# atmg32.net
KiCad netlist of a schematic drawn in Altium Designer
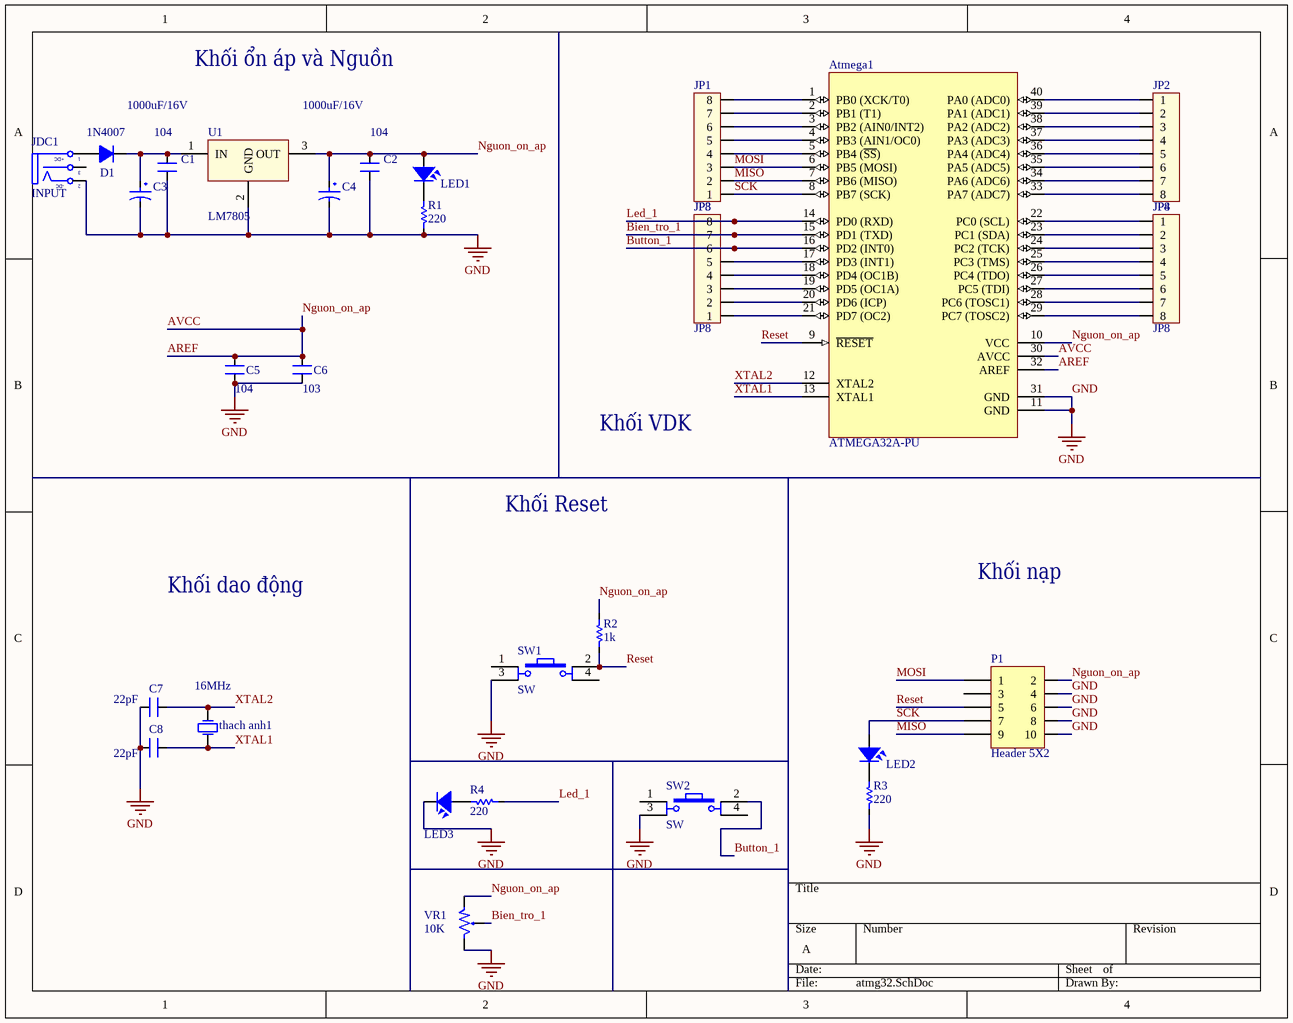
[diagram p0: atmg32.SchDoc]

(export (version "E")
  (design (tool "Eeschema 10.0.6"))
  (components
    (comp (ref "Atmega1")
      (value "ATMEGA32A-PU")
      (footprint "DIP 40")
      (description "8-Bit AVR Microcontroller with 32K Bytes of In-System Programmable Flash Memory")
      (fields (field (name "PUBLISHER") "Altium Limited"))
      (libsource (lib "Library_NguyenThanhPhong") (part "ATMEGA32A-PU"))
    )
    (comp (ref "C1")
      (value "104")
      (footprint "CN0")
      (description "Ceramic capacitor")
      (libsource (lib "Library_NguyenThanhPhong") (part "CN0"))
    )
    (comp (ref "C2")
      (value "104")
      (footprint "CN0")
      (description "Ceramic capacitor")
      (libsource (lib "Library_NguyenThanhPhong") (part "CN0"))
    )
    (comp (ref "C3")
      (value "1000uF/16V")
      (footprint "CAP 10x16x5 CURVE")
      (libsource (lib "Library_NguyenThanhPhong") (part "CAP 10x16mm"))
    )
    (comp (ref "C4")
      (value "1000uF/16V")
      (footprint "CAP 10x16x5 CURVE")
      (libsource (lib "Library_NguyenThanhPhong") (part "CAP 10x16mm"))
    )
    (comp (ref "C5")
      (value "104")
      (footprint "CN0")
      (description "Ceramic capacitor")
      (libsource (lib "Library_NguyenThanhPhong") (part "CN0"))
    )
    (comp (ref "C6")
      (value "103")
      (footprint "CN0")
      (description "Ceramic capacitor")
      (libsource (lib "Library_NguyenThanhPhong") (part "CN0"))
    )
    (comp (ref "C7")
      (value "22pF")
      (footprint "CN0")
      (description "Ceramic capacitor")
      (libsource (lib "Library_NguyenThanhPhong") (part "CN0"))
    )
    (comp (ref "C8")
      (value "22pF")
      (footprint "CN0")
      (description "Ceramic capacitor")
      (libsource (lib "Library_NguyenThanhPhong") (part "CN0"))
    )
    (comp (ref "D1")
      (value "1N4007")
      (footprint "1N4007")
      (description "Diode 1N4007 1A 1000V")
      (libsource (lib "Library_NguyenThanhPhong") (part "1N4007"))
    )
    (comp (ref "JDC1")
      (value "INPUT")
      (footprint "DC-IN")
      (description "Jac DC input")
      (libsource (lib "Library_NguyenThanhPhong") (part "DCIN"))
    )
    (comp (ref "JP1")
      (value "JP8")
      (footprint "XH2.54-8P")
      (description "Header duc 8, Connector 8, Header 8")
      (libsource (lib "Library_NguyenThanhPhong") (part "Con8"))
    )
    (comp (ref "JP2")
      (value "JP8")
      (footprint "XH2.54-8P")
      (description "Header duc 8, Connector 8, Header 8")
      (libsource (lib "") (part "Con8_1"))
    )
    (comp (ref "JP3")
      (value "JP8")
      (footprint "XH2.54-8P")
      (description "Header duc 8, Connector 8, Header 8")
      (libsource (lib "Library_NguyenThanhPhong") (part "Con8"))
    )
    (comp (ref "JP4")
      (value "JP8")
      (footprint "XH2.54-8P")
      (description "Header duc 8, Connector 8, Header 8")
      (libsource (lib "") (part "Con8_1"))
    )
    (comp (ref "LED1")
      (value "LED")
      (footprint "LED-5MM-WHITE")
      (description "LED Single")
      (libsource (lib "Library_NguyenThanhPhong") (part "LED"))
    )
    (comp (ref "LED2")
      (value "LED")
      (footprint "LED-5MM-WHITE")
      (description "LED Single")
      (libsource (lib "Library_NguyenThanhPhong") (part "LED"))
    )
    (comp (ref "LED3")
      (value "LED")
      (footprint "LED-5MM-WHITE")
      (description "LED Single")
      (libsource (lib "Library_NguyenThanhPhong") (part "LED"))
    )
    (comp (ref "P1")
      (value "Header 5X2")
      (footprint "HDR2X5")
      (description "Header, 5-Pin, Dual row")
      (fields (field (name "PUBLISHER") "Altium Limited"))
      (libsource (lib "Miscellaneous Connectors") (part "Header 5X2"))
    )
    (comp (ref "R1")
      (value "220")
      (footprint "RES-1/4W")
      (description "Tro cam")
      (libsource (lib "Library_NguyenThanhPhong") (part "Res1/4W"))
    )
    (comp (ref "R2")
      (value "1k")
      (footprint "RES-1/4W")
      (description "Tro cam")
      (libsource (lib "Library_NguyenThanhPhong") (part "Res1/4W"))
    )
    (comp (ref "R3")
      (value "220")
      (footprint "RES-1/4W")
      (description "Tro cam")
      (libsource (lib "Library_NguyenThanhPhong") (part "Res1/4W"))
    )
    (comp (ref "R4")
      (value "220")
      (footprint "RES-1/4W")
      (description "Tro cam")
      (libsource (lib "Library_NguyenThanhPhong") (part "Res1/4W"))
    )
    (comp (ref "SW1")
      (value "SW")
      (footprint "BUTTON 12x12x5 4P DIP")
      (description "Switch button 4 pin 12x12mm")
      (libsource (lib "Library_NguyenThanhPhong") (part "SW4 12x12"))
    )
    (comp (ref "SW2")
      (value "SW")
      (footprint "BUTTON 12x12x5 4P DIP")
      (description "Switch button 4 pin 12x12mm")
      (libsource (lib "Library_NguyenThanhPhong") (part "SW4 12x12"))
    )
    (comp (ref "thach anh1")
      (value "16MHz")
      (footprint "CRYSTAL DIP")
      (description "Thach anh")
      (fields (field (name "PUBLISHER") "Altium Limited"))
      (libsource (lib "Library_NguyenThanhPhong") (part "Crystal"))
    )
    (comp (ref "U1")
      (value "LM7805")
      (footprint "TO 220+Heatsink 21x15x10mm")
      (description "On ap +, from + 5 to + 24VDC")
      (libsource (lib "Library_NguyenThanhPhong") (part "LM78xx"))
    )
    (comp (ref "VR1")
      (value "10K")
      (footprint "VR-RM065")
      (description "Var Resistor")
      (libsource (lib "Library_NguyenThanhPhong") (part "VR"))
    )
  )
  (nets
    (net (code "1") (name "/AREF") (class "Default")
      (node (ref "Atmega1") (pin "10") (pinfunction "VCC_10") (pintype "power_in"))
      (node (ref "Atmega1") (pin "30") (pinfunction "AVCC_30") (pintype "power_in"))
      (node (ref "Atmega1") (pin "32") (pinfunction "AREF_32") (pintype "passive"))
      (node (ref "C2") (pin "2") (pinfunction "2_2") (pintype "passive"))
      (node (ref "C4") (pin "1") (pinfunction "1_1") (pintype "passive"))
      (node (ref "C5") (pin "2") (pinfunction "2_2") (pintype "passive"))
      (node (ref "C6") (pin "2") (pinfunction "2_2") (pintype "passive"))
      (node (ref "LED1") (pin "1") (pinfunction "1_1") (pintype "passive"))
      (node (ref "P1") (pin "2") (pinfunction "2_2") (pintype "passive"))
      (node (ref "R2") (pin "2") (pinfunction "2_2") (pintype "passive"))
      (node (ref "U1") (pin "3") (pinfunction "OUT_3") (pintype "passive"))
      (node (ref "VR1") (pin "1") (pinfunction "1_1") (pintype "passive"))
    )
    (net (code "2") (name "/Bien_tro_1") (class "Default")
      (node (ref "Atmega1") (pin "15") (pinfunction "PD1_(TXD)_15") (pintype "bidirectional"))
      (node (ref "JP3") (pin "7") (pinfunction "7_7") (pintype "passive"))
      (node (ref "VR1") (pin "2") (pinfunction "2_2") (pintype "passive"))
    )
    (net (code "3") (name "/Button_1") (class "Default")
      (node (ref "Atmega1") (pin "16") (pinfunction "PD2_(INT0)_16") (pintype "bidirectional"))
      (node (ref "JP3") (pin "6") (pinfunction "6_6") (pintype "passive"))
      (node (ref "SW2") (pin "2") (pintype "passive"))
    )
    (net (code "4") (name "/Led_1") (class "Default")
      (node (ref "Atmega1") (pin "14") (pinfunction "PD0_(RXD)_14") (pintype "bidirectional"))
      (node (ref "JP3") (pin "8") (pinfunction "8_8") (pintype "passive"))
      (node (ref "R4") (pin "1") (pinfunction "1_1") (pintype "passive"))
    )
    (net (code "5") (name "/MISO") (class "Default")
      (node (ref "Atmega1") (pin "7") (pinfunction "PB6_(MISO)_7") (pintype "bidirectional"))
      (node (ref "JP1") (pin "2") (pinfunction "2_2") (pintype "passive"))
      (node (ref "P1") (pin "9") (pinfunction "9_9") (pintype "passive"))
    )
    (net (code "6") (name "/MOSI") (class "Default")
      (node (ref "Atmega1") (pin "6") (pinfunction "PB5_(MOSI)_6") (pintype "bidirectional"))
      (node (ref "JP1") (pin "3") (pinfunction "3_3") (pintype "passive"))
      (node (ref "P1") (pin "1") (pinfunction "1_1") (pintype "passive"))
    )
    (net (code "7") (name "/Reset") (class "Default")
      (node (ref "Atmega1") (pin "9") (pinfunction "~{RESET}_9") (pintype "input"))
      (node (ref "P1") (pin "5") (pinfunction "5_5") (pintype "passive"))
      (node (ref "R2") (pin "1") (pinfunction "1_1") (pintype "passive"))
      (node (ref "SW1") (pin "2") (pintype "passive"))
    )
    (net (code "8") (name "/SCK") (class "Default")
      (node (ref "Atmega1") (pin "8") (pinfunction "PB7_(SCK)_8") (pintype "bidirectional"))
      (node (ref "JP1") (pin "1") (pinfunction "1_1") (pintype "passive"))
      (node (ref "LED2") (pin "1") (pinfunction "1_1") (pintype "passive"))
      (node (ref "P1") (pin "7") (pinfunction "7_7") (pintype "passive"))
    )
    (net (code "9") (name "/XTAL1") (class "Default")
      (node (ref "Atmega1") (pin "13") (pinfunction "XTAL1_13") (pintype "passive"))
      (node (ref "C8") (pin "1") (pinfunction "1_1") (pintype "passive"))
      (node (ref "thach anh1") (pin "1") (pinfunction "OSC1_1") (pintype "passive"))
    )
    (net (code "10") (name "/XTAL2") (class "Default")
      (node (ref "Atmega1") (pin "12") (pinfunction "XTAL2_12") (pintype "passive"))
      (node (ref "C7") (pin "1") (pinfunction "1_1") (pintype "passive"))
      (node (ref "thach anh1") (pin "2") (pinfunction "OSC2_2") (pintype "passive"))
    )
    (net (code "11") (name "GND") (class "Default")
      (node (ref "Atmega1") (pin "11") (pinfunction "GND_11") (pintype "power_in"))
      (node (ref "Atmega1") (pin "31") (pinfunction "GND_31") (pintype "power_in"))
      (node (ref "C1") (pin "1") (pinfunction "1_1") (pintype "passive"))
      (node (ref "C2") (pin "1") (pinfunction "1_1") (pintype "passive"))
      (node (ref "C3") (pin "2") (pinfunction "2_2") (pintype "passive"))
      (node (ref "C4") (pin "2") (pinfunction "2_2") (pintype "passive"))
      (node (ref "C5") (pin "1") (pinfunction "1_1") (pintype "passive"))
      (node (ref "C6") (pin "1") (pinfunction "1_1") (pintype "passive"))
      (node (ref "C7") (pin "2") (pinfunction "2_2") (pintype "passive"))
      (node (ref "C8") (pin "2") (pinfunction "2_2") (pintype "passive"))
      (node (ref "JDC1") (pin "2") (pinfunction "TN_2") (pintype "passive"))
      (node (ref "LED3") (pin "2") (pinfunction "2_2") (pintype "passive"))
      (node (ref "P1") (pin "10") (pinfunction "10_10") (pintype "passive"))
      (node (ref "P1") (pin "4") (pinfunction "4_4") (pintype "passive"))
      (node (ref "P1") (pin "6") (pinfunction "6_6") (pintype "passive"))
      (node (ref "P1") (pin "8") (pinfunction "8_8") (pintype "passive"))
      (node (ref "R1") (pin "1") (pinfunction "1_1") (pintype "passive"))
      (node (ref "R3") (pin "1") (pinfunction "1_1") (pintype "passive"))
      (node (ref "SW1") (pin "3") (pintype "passive"))
      (node (ref "SW2") (pin "3") (pintype "passive"))
      (node (ref "U1") (pin "2") (pinfunction "GND_2") (pintype "passive"))
      (node (ref "VR1") (pin "3") (pinfunction "3_3") (pintype "passive"))
    )
    (net (code "12") (name "Net-(Atmega1-PA0_(ADC0))") (class "Default")
      (node (ref "Atmega1") (pin "40") (pinfunction "PA0_(ADC0)_40") (pintype "bidirectional"))
      (node (ref "JP2") (pin "1") (pinfunction "1_1") (pintype "passive"))
    )
    (net (code "13") (name "Net-(Atmega1-PA1_(ADC1))") (class "Default")
      (node (ref "Atmega1") (pin "39") (pinfunction "PA1_(ADC1)_39") (pintype "bidirectional"))
      (node (ref "JP2") (pin "2") (pinfunction "2_2") (pintype "passive"))
    )
    (net (code "14") (name "Net-(Atmega1-PA2_(ADC2))") (class "Default")
      (node (ref "Atmega1") (pin "38") (pinfunction "PA2_(ADC2)_38") (pintype "bidirectional"))
      (node (ref "JP2") (pin "3") (pinfunction "3_3") (pintype "passive"))
    )
    (net (code "15") (name "Net-(Atmega1-PA3_(ADC3))") (class "Default")
      (node (ref "Atmega1") (pin "37") (pinfunction "PA3_(ADC3)_37") (pintype "bidirectional"))
      (node (ref "JP2") (pin "4") (pinfunction "4_4") (pintype "passive"))
    )
    (net (code "16") (name "Net-(Atmega1-PA4_(ADC4))") (class "Default")
      (node (ref "Atmega1") (pin "36") (pinfunction "PA4_(ADC4)_36") (pintype "bidirectional"))
      (node (ref "JP2") (pin "5") (pinfunction "5_5") (pintype "passive"))
    )
    (net (code "17") (name "Net-(Atmega1-PA5_(ADC5))") (class "Default")
      (node (ref "Atmega1") (pin "35") (pinfunction "PA5_(ADC5)_35") (pintype "bidirectional"))
      (node (ref "JP2") (pin "6") (pinfunction "6_6") (pintype "passive"))
    )
    (net (code "18") (name "Net-(Atmega1-PA6_(ADC6))") (class "Default")
      (node (ref "Atmega1") (pin "34") (pinfunction "PA6_(ADC6)_34") (pintype "bidirectional"))
      (node (ref "JP2") (pin "7") (pinfunction "7_7") (pintype "passive"))
    )
    (net (code "19") (name "Net-(Atmega1-PA7_(ADC7))") (class "Default")
      (node (ref "Atmega1") (pin "33") (pinfunction "PA7_(ADC7)_33") (pintype "bidirectional"))
      (node (ref "JP2") (pin "8") (pinfunction "8_8") (pintype "passive"))
    )
    (net (code "20") (name "Net-(Atmega1-PB0_(XCK{slash}T0))") (class "Default")
      (node (ref "Atmega1") (pin "1") (pinfunction "PB0_(XCK/T0)_1") (pintype "bidirectional"))
      (node (ref "JP1") (pin "8") (pinfunction "8_8") (pintype "passive"))
    )
    (net (code "21") (name "Net-(Atmega1-PB1_(T1))") (class "Default")
      (node (ref "Atmega1") (pin "2") (pinfunction "PB1_(T1)_2") (pintype "bidirectional"))
      (node (ref "JP1") (pin "7") (pinfunction "7_7") (pintype "passive"))
    )
    (net (code "22") (name "Net-(Atmega1-PB2_(AIN0{slash}INT2))") (class "Default")
      (node (ref "Atmega1") (pin "3") (pinfunction "PB2_(AIN0/INT2)_3") (pintype "bidirectional"))
      (node (ref "JP1") (pin "6") (pinfunction "6_6") (pintype "passive"))
    )
    (net (code "23") (name "Net-(Atmega1-PB3_(AIN1{slash}OC0))") (class "Default")
      (node (ref "Atmega1") (pin "4") (pinfunction "PB3_(AIN1/OC0)_4") (pintype "bidirectional"))
      (node (ref "JP1") (pin "5") (pinfunction "5_5") (pintype "passive"))
    )
    (net (code "24") (name "Net-(Atmega1-PB4_(~{SS}))") (class "Default")
      (node (ref "Atmega1") (pin "5") (pinfunction "PB4_(~{SS})_5") (pintype "bidirectional"))
      (node (ref "JP1") (pin "4") (pinfunction "4_4") (pintype "passive"))
    )
    (net (code "25") (name "Net-(Atmega1-PC0_(SCL))") (class "Default")
      (node (ref "Atmega1") (pin "22") (pinfunction "PC0_(SCL)_22") (pintype "bidirectional"))
      (node (ref "JP4") (pin "1") (pinfunction "1_1") (pintype "passive"))
    )
    (net (code "26") (name "Net-(Atmega1-PC1_(SDA))") (class "Default")
      (node (ref "Atmega1") (pin "23") (pinfunction "PC1_(SDA)_23") (pintype "bidirectional"))
      (node (ref "JP4") (pin "2") (pinfunction "2_2") (pintype "passive"))
    )
    (net (code "27") (name "Net-(Atmega1-PC2_(TCK))") (class "Default")
      (node (ref "Atmega1") (pin "24") (pinfunction "PC2_(TCK)_24") (pintype "bidirectional"))
      (node (ref "JP4") (pin "3") (pinfunction "3_3") (pintype "passive"))
    )
    (net (code "28") (name "Net-(Atmega1-PC3_(TMS))") (class "Default")
      (node (ref "Atmega1") (pin "25") (pinfunction "PC3_(TMS)_25") (pintype "bidirectional"))
      (node (ref "JP4") (pin "4") (pinfunction "4_4") (pintype "passive"))
    )
    (net (code "29") (name "Net-(Atmega1-PC4_(TDO))") (class "Default")
      (node (ref "Atmega1") (pin "26") (pinfunction "PC4_(TDO)_26") (pintype "bidirectional"))
      (node (ref "JP4") (pin "5") (pinfunction "5_5") (pintype "passive"))
    )
    (net (code "30") (name "Net-(Atmega1-PC5_(TDI))") (class "Default")
      (node (ref "Atmega1") (pin "27") (pinfunction "PC5_(TDI)_27") (pintype "bidirectional"))
      (node (ref "JP4") (pin "6") (pinfunction "6_6") (pintype "passive"))
    )
    (net (code "31") (name "Net-(Atmega1-PC6_(TOSC1))") (class "Default")
      (node (ref "Atmega1") (pin "28") (pinfunction "PC6_(TOSC1)_28") (pintype "bidirectional"))
      (node (ref "JP4") (pin "7") (pinfunction "7_7") (pintype "passive"))
    )
    (net (code "32") (name "Net-(Atmega1-PC7_(TOSC2))") (class "Default")
      (node (ref "Atmega1") (pin "29") (pinfunction "PC7_(TOSC2)_29") (pintype "bidirectional"))
      (node (ref "JP4") (pin "8") (pinfunction "8_8") (pintype "passive"))
    )
    (net (code "33") (name "Net-(Atmega1-PD3_(INT1))") (class "Default")
      (node (ref "Atmega1") (pin "17") (pinfunction "PD3_(INT1)_17") (pintype "bidirectional"))
      (node (ref "JP3") (pin "5") (pinfunction "5_5") (pintype "passive"))
    )
    (net (code "34") (name "Net-(Atmega1-PD4_(OC1B))") (class "Default")
      (node (ref "Atmega1") (pin "18") (pinfunction "PD4_(OC1B)_18") (pintype "bidirectional"))
      (node (ref "JP3") (pin "4") (pinfunction "4_4") (pintype "passive"))
    )
    (net (code "35") (name "Net-(Atmega1-PD5_(OC1A))") (class "Default")
      (node (ref "Atmega1") (pin "19") (pinfunction "PD5_(OC1A)_19") (pintype "bidirectional"))
      (node (ref "JP3") (pin "3") (pinfunction "3_3") (pintype "passive"))
    )
    (net (code "36") (name "Net-(Atmega1-PD6_(ICP))") (class "Default")
      (node (ref "Atmega1") (pin "20") (pinfunction "PD6_(ICP)_20") (pintype "bidirectional"))
      (node (ref "JP3") (pin "2") (pinfunction "2_2") (pintype "passive"))
    )
    (net (code "37") (name "Net-(Atmega1-PD7_(OC2))") (class "Default")
      (node (ref "Atmega1") (pin "21") (pinfunction "PD7_(OC2)_21") (pintype "bidirectional"))
      (node (ref "JP3") (pin "1") (pinfunction "1_1") (pintype "passive"))
    )
    (net (code "38") (name "Net-(D1-A)") (class "Default")
      (node (ref "D1") (pin "1") (pinfunction "A_1") (pintype "passive"))
      (node (ref "JDC1") (pin "1") (pinfunction "T_1") (pintype "passive"))
    )
    (net (code "39") (name "Net-(D1-K)") (class "Default")
      (node (ref "C1") (pin "2") (pinfunction "2_2") (pintype "passive"))
      (node (ref "C3") (pin "1") (pinfunction "1_1") (pintype "passive"))
      (node (ref "D1") (pin "2") (pinfunction "K_2") (pintype "passive"))
      (node (ref "U1") (pin "1") (pinfunction "IN_1") (pintype "passive"))
    )
    (net (code "40") (name "Net-(LED1-Pad2)") (class "Default")
      (node (ref "LED1") (pin "2") (pinfunction "2_2") (pintype "passive"))
      (node (ref "R1") (pin "2") (pinfunction "2_2") (pintype "passive"))
    )
    (net (code "41") (name "Net-(LED2-Pad2)") (class "Default")
      (node (ref "LED2") (pin "2") (pinfunction "2_2") (pintype "passive"))
      (node (ref "R3") (pin "2") (pinfunction "2_2") (pintype "passive"))
    )
    (net (code "42") (name "Net-(LED3-Pad1)") (class "Default")
      (node (ref "LED3") (pin "1") (pinfunction "1_1") (pintype "passive"))
      (node (ref "R4") (pin "2") (pinfunction "2_2") (pintype "passive"))
    )
    (net (code "43") (name "unconnected-(JDC1-S-Pad3)") (class "Default")
      (node (ref "JDC1") (pin "3") (pinfunction "S_3") (pintype "power_in"))
    )
    (net (code "44") (name "unconnected-(P1-Pad3)") (class "Default")
      (node (ref "P1") (pin "3") (pinfunction "3_3") (pintype "passive"))
    )
    (net (code "45") (name "unconnected-(SW1-Pad1)") (class "Default")
      (node (ref "SW1") (pin "1") (pintype "passive"))
    )
    (net (code "46") (name "unconnected-(SW1-Pad4)") (class "Default")
      (node (ref "SW1") (pin "4") (pintype "passive"))
    )
    (net (code "47") (name "unconnected-(SW2-Pad1)") (class "Default")
      (node (ref "SW2") (pin "1") (pintype "passive"))
    )
    (net (code "48") (name "unconnected-(SW2-Pad4)") (class "Default")
      (node (ref "SW2") (pin "4") (pintype "passive"))
    )
  )
)
